# Main.net
KiCad netlist of a schematic drawn in Altium Designer
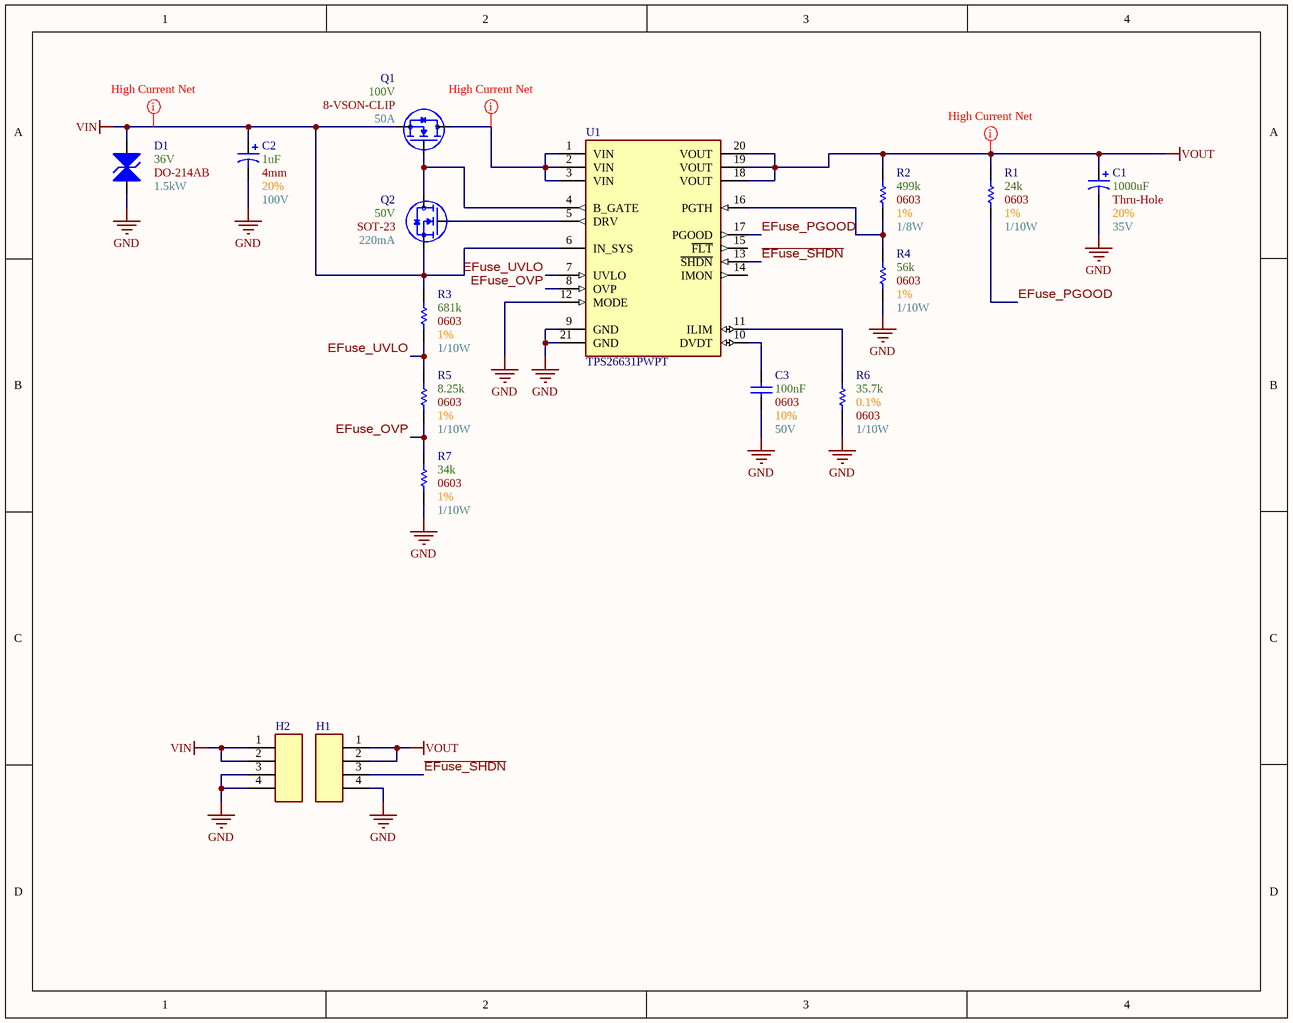
[diagram p0: Main.SchDoc]

(export (version "E")
  (design (tool "Eeschema 10.0.6"))
  (components
    (comp (ref "C1")
      (value "[Cap] Thru-Hole 1000uF 20% 35V")
      (footprint "[Cap] Thru-Hole Polarized 10mm")
      (description "35PK1000MEFC10X20")
      (fields
        (field (name "MAX VOLTAGE") "35V")
        (field (name "SIZE PACKAGE") "Thru-Hole")
        (field (name "TOLERANCE") "20%")
        (field (name "CAPACITANCE") "1000uF")
      )
      (libsource (lib "Capacitors") (part "[Cap] Thru-Hole 1000uF 20% 35V"))
    )
    (comp (ref "C2")
      (value "[Cap] 4mm 1uF 20% 100V")
      (footprint "[Cap] SMD Polarized, 4mm")
      (description "865080840001")
      (fields
        (field (name "MAX VOLTAGE") "100V")
        (field (name "SIZE PACKAGE") "4mm")
        (field (name "TOLERANCE") "20%")
        (field (name "CAPACITANCE") "1uF")
      )
      (libsource (lib "Capacitors") (part "[Cap] 4mm 1uF 20% 100V"))
    )
    (comp (ref "C3")
      (value "[Cap] 0603 0.1uF 10% 50V")
      (footprint "[Cap] SMD 0603")
      (description "CL10B104KB8NNNC")
      (fields
        (field (name "MAX VOLTAGE") "50V")
        (field (name "SIZE PACKAGE") "0603")
        (field (name "TOLERANCE") "10%")
        (field (name "CAPACITANCE") "100nF")
      )
      (libsource (lib "Capacitors") (part "[Cap] 0603 0.1uF 10% 50V"))
    )
    (comp (ref "D1")
      (value "DO-214AB")
      (footprint "DO-214AB")
      (description "SMCJ36CA")
      (fields (field (name "WATTAGE") "1.5kW") (field (name "OPTIMAL ZENER VOLTAGE") "36V"))
      (libsource (lib "Diodes") (part "[TVS] 36Vnom 40Vclamp_max"))
    )
    (comp (ref "H1")
      (value "1x4 Header")
      (footprint "[Header] 1x4 Male")
      (description "2.54mm pitch")
      (libsource (lib "") (part "[Header] 1x4 Male_1"))
    )
    (comp (ref "H2")
      (value "1x4 Header")
      (footprint "[Header] 1x4 Male")
      (description "2.54mm pitch")
      (libsource (lib "Connectors") (part "[Header] 1x4 Male"))
    )
    (comp (ref "Q1")
      (value "CSD19537Q3")
      (footprint "8-VSON-CLIP")
      (fields
        (field (name "IDS_MAX") "50A")
        (field (name "PACKAGE") "8-VSON-CLIP")
        (field (name "VDS_MAX") "100V")
      )
      (libsource (lib "Transistors") (part "[NMOS] SMD 100V 50A 14.5mOhm"))
    )
    (comp (ref "Q2")
      (value "[NMOS] SMD 50V 220mA 3Ohm")
      (footprint "SOT-23")
      (description "BSS138")
      (fields
        (field (name "IDS_MAX") "220mA")
        (field (name "PACKAGE") "SOT-23")
        (field (name "VDS_MAX") "50V")
      )
      (libsource (lib "Transistors") (part "[NMOS] SMD 50V 220mA 3Ohm"))
    )
    (comp (ref "R1")
      (value "[24k] SMD 0603 1% 1/10W")
      (footprint "[Res] SMD 0603")
      (description "RC0603FR-1324KL")
      (fields
        (field (name "WATTAGE") "1/10W")
        (field (name "TOLERANCE") "1%")
        (field (name "RESISTANCE") "24k")
        (field (name "SIZE PACKAGE") "0603")
      )
      (libsource (lib "Resistors") (part "[24k] SMD 0603 1% 1/10W"))
    )
    (comp (ref "R2")
      (value "[499k] SMD 0603 1% 1/8W")
      (footprint "[Res] SMD 0603")
      (description "CRCW0603499KFKEA")
      (fields
        (field (name "WATTAGE") "1/8W")
        (field (name "TOLERANCE") "1%")
        (field (name "RESISTANCE") "499k")
        (field (name "SIZE PACKAGE") "0603")
      )
      (libsource (lib "Resistors") (part "[499k] SMD 0603 1% 1/8W"))
    )
    (comp (ref "R3")
      (value "[681k] SMD 0603 1% 1/10W")
      (footprint "[Res] SMD 0603")
      (description "RT0603FRE07681KL")
      (fields
        (field (name "WATTAGE") "1/10W")
        (field (name "TOLERANCE") "1%")
        (field (name "RESISTANCE") "681k")
        (field (name "SIZE PACKAGE") "0603")
      )
      (libsource (lib "Resistors") (part "[681k] SMD 0603 1% 1/10W"))
    )
    (comp (ref "R4")
      (value "[56k] SMD 0603 1% 1/10W")
      (footprint "[Res] SMD 0603")
      (description "CRGCQ0603F56K")
      (fields
        (field (name "WATTAGE") "1/10W")
        (field (name "TOLERANCE") "1%")
        (field (name "RESISTANCE") "56k")
        (field (name "SIZE PACKAGE") "0603")
      )
      (libsource (lib "Resistors") (part "[56k] SMD 0603 1% 1/10W"))
    )
    (comp (ref "R5")
      (value "[8.25k] SMD 0603 1% 1/10W")
      (footprint "[Res] SMD 0603")
      (description "AF0603FR-078K25L")
      (fields
        (field (name "WATTAGE") "1/10W")
        (field (name "TOLERANCE") "1%")
        (field (name "RESISTANCE") "8.25k")
        (field (name "SIZE PACKAGE") "0603")
      )
      (libsource (lib "Resistors") (part "[8.25k] SMD 0603 1% 1/10W"))
    )
    (comp (ref "R6")
      (value "[35.7k] SMD 0603 0.1% 1/10W")
      (footprint "[Res] SMD 0603")
      (description "RT0603BRE0735K7L")
      (fields
        (field (name "WATTAGE") "1/10W")
        (field (name "TOLERANCE") "0.1%")
        (field (name "RESISTANCE") "35.7k")
        (field (name "SIZE PACKAGE") "0603")
      )
      (libsource (lib "Resistors") (part "[35.7k] SMD 0603 0.1% 1/10W"))
    )
    (comp (ref "R7")
      (value "[34k] SMD 0603 1% 1/10W")
      (footprint "[Res] SMD 0603")
      (description "RC0603FR-1334KL")
      (fields
        (field (name "WATTAGE") "1/10W")
        (field (name "TOLERANCE") "1%")
        (field (name "RESISTANCE") "34k")
        (field (name "SIZE PACKAGE") "0603")
      )
      (libsource (lib "Resistors") (part "[34k] SMD 0603 1% 1/10W"))
    )
    (comp (ref "U1")
      (value "TPS26631PWPT")
      (footprint "[E-Fuse] 4.5-60V 6A")
      (libsource (lib "ICs") (part "[E-Fuse] 4.5-60V 6A"))
    )
  )
  (nets
    (net (code "1") (name "/EFuse_OVP") (class "Default")
      (node (ref "R5") (pin "1") (pinfunction "1_1") (pintype "passive"))
      (node (ref "R7") (pin "2") (pinfunction "2_2") (pintype "passive"))
      (node (ref "U1") (pin "8") (pinfunction "OVP_8") (pintype "input"))
    )
    (net (code "2") (name "/EFuse_PGOOD") (class "Default")
      (node (ref "R1") (pin "1") (pinfunction "1_1") (pintype "passive"))
      (node (ref "U1") (pin "17") (pinfunction "PGOOD_17") (pintype "output"))
    )
    (net (code "3") (name "/EFuse_SHDN") (class "Default")
      (node (ref "H1") (pin "3") (pintype "passive"))
      (node (ref "U1") (pin "13") (pinfunction "~{SHDN}_13") (pintype "input"))
    )
    (net (code "4") (name "/EFuse_UVLO") (class "Default")
      (node (ref "R3") (pin "1") (pinfunction "1_1") (pintype "passive"))
      (node (ref "R5") (pin "2") (pinfunction "2_2") (pintype "passive"))
      (node (ref "U1") (pin "7") (pinfunction "UVLO_7") (pintype "input"))
    )
    (net (code "5") (name "GND") (class "Default")
      (node (ref "C1") (pin "2") (pinfunction "2_2") (pintype "passive"))
      (node (ref "C2") (pin "2") (pinfunction "2_2") (pintype "passive"))
      (node (ref "C3") (pin "1") (pinfunction "1_1") (pintype "passive"))
      (node (ref "D1") (pin "2") (pinfunction "A_2") (pintype "passive"))
      (node (ref "H1") (pin "4") (pintype "passive"))
      (node (ref "H2") (pin "3") (pintype "passive"))
      (node (ref "H2") (pin "4") (pintype "passive"))
      (node (ref "R4") (pin "1") (pinfunction "1_1") (pintype "passive"))
      (node (ref "R6") (pin "1") (pinfunction "1_1") (pintype "passive"))
      (node (ref "R7") (pin "1") (pinfunction "1_1") (pintype "passive"))
      (node (ref "U1") (pin "12") (pinfunction "MODE_12") (pintype "input"))
      (node (ref "U1") (pin "21") (pinfunction "GND_21") (pintype "power_in"))
      (node (ref "U1") (pin "9") (pinfunction "GND_9") (pintype "passive"))
    )
    (net (code "6") (name "Net-(Q1-Drain)") (class "Default")
      (node (ref "Q1") (pin "3") (pinfunction "Drain_3") (pintype "passive"))
      (node (ref "U1") (pin "1") (pinfunction "VIN_1") (pintype "passive"))
      (node (ref "U1") (pin "2") (pinfunction "VIN_2") (pintype "passive"))
      (node (ref "U1") (pin "3") (pinfunction "VIN_3") (pintype "passive"))
    )
    (net (code "7") (name "Net-(Q1-Gate)") (class "Default")
      (node (ref "Q1") (pin "1") (pinfunction "Gate_1") (pintype "passive"))
      (node (ref "Q2") (pin "3") (pinfunction "Drain_3") (pintype "passive"))
      (node (ref "U1") (pin "4") (pinfunction "B_GATE_4") (pintype "output"))
    )
    (net (code "8") (name "Net-(Q2-Gate)") (class "Default")
      (node (ref "Q2") (pin "1") (pinfunction "Gate_1") (pintype "passive"))
      (node (ref "U1") (pin "5") (pinfunction "DRV_5") (pintype "output"))
    )
    (net (code "9") (name "Net-(U1-DVDT)") (class "Default")
      (node (ref "C3") (pin "2") (pinfunction "2_2") (pintype "passive"))
      (node (ref "U1") (pin "10") (pinfunction "DVDT_10") (pintype "bidirectional"))
    )
    (net (code "10") (name "Net-(U1-ILIM)") (class "Default")
      (node (ref "R6") (pin "2") (pinfunction "2_2") (pintype "passive"))
      (node (ref "U1") (pin "11") (pinfunction "ILIM_11") (pintype "bidirectional"))
    )
    (net (code "11") (name "Net-(U1-PGTH)") (class "Default")
      (node (ref "R2") (pin "1") (pinfunction "1_1") (pintype "passive"))
      (node (ref "R4") (pin "2") (pinfunction "2_2") (pintype "passive"))
      (node (ref "U1") (pin "16") (pinfunction "PGTH_16") (pintype "input"))
    )
    (net (code "12") (name "VIN") (class "Default")
      (node (ref "C2") (pin "1") (pinfunction "1_1") (pintype "passive"))
      (node (ref "D1") (pin "1") (pinfunction "K_1") (pintype "passive"))
      (node (ref "H2") (pin "1") (pintype "passive"))
      (node (ref "H2") (pin "2") (pintype "passive"))
      (node (ref "Q1") (pin "2") (pinfunction "Source_2") (pintype "passive"))
      (node (ref "Q2") (pin "2") (pinfunction "Source_2") (pintype "passive"))
      (node (ref "R3") (pin "2") (pinfunction "2_2") (pintype "passive"))
      (node (ref "U1") (pin "6") (pinfunction "IN_SYS_6") (pintype "power_in"))
    )
    (net (code "13") (name "VOUT") (class "Default")
      (node (ref "C1") (pin "1") (pinfunction "1_1") (pintype "passive"))
      (node (ref "H1") (pin "1") (pintype "passive"))
      (node (ref "H1") (pin "2") (pintype "passive"))
      (node (ref "R1") (pin "2") (pinfunction "2_2") (pintype "passive"))
      (node (ref "R2") (pin "2") (pinfunction "2_2") (pintype "passive"))
      (node (ref "U1") (pin "18") (pinfunction "VOUT_18") (pintype "passive"))
      (node (ref "U1") (pin "19") (pinfunction "VOUT_19") (pintype "passive"))
      (node (ref "U1") (pin "20") (pinfunction "VOUT_20") (pintype "passive"))
    )
    (net (code "14") (name "unconnected-(U1-IMON-Pad14)") (class "Default")
      (node (ref "U1") (pin "14") (pinfunction "IMON_14") (pintype "output"))
    )
    (net (code "15") (name "unconnected-(U1-~{FLT}-Pad15)") (class "Default")
      (node (ref "U1") (pin "15") (pinfunction "~{FLT}_15") (pintype "output"))
    )
  )
)
